# bridge.net
KiCad netlist of a schematic drawn in Altium Designer
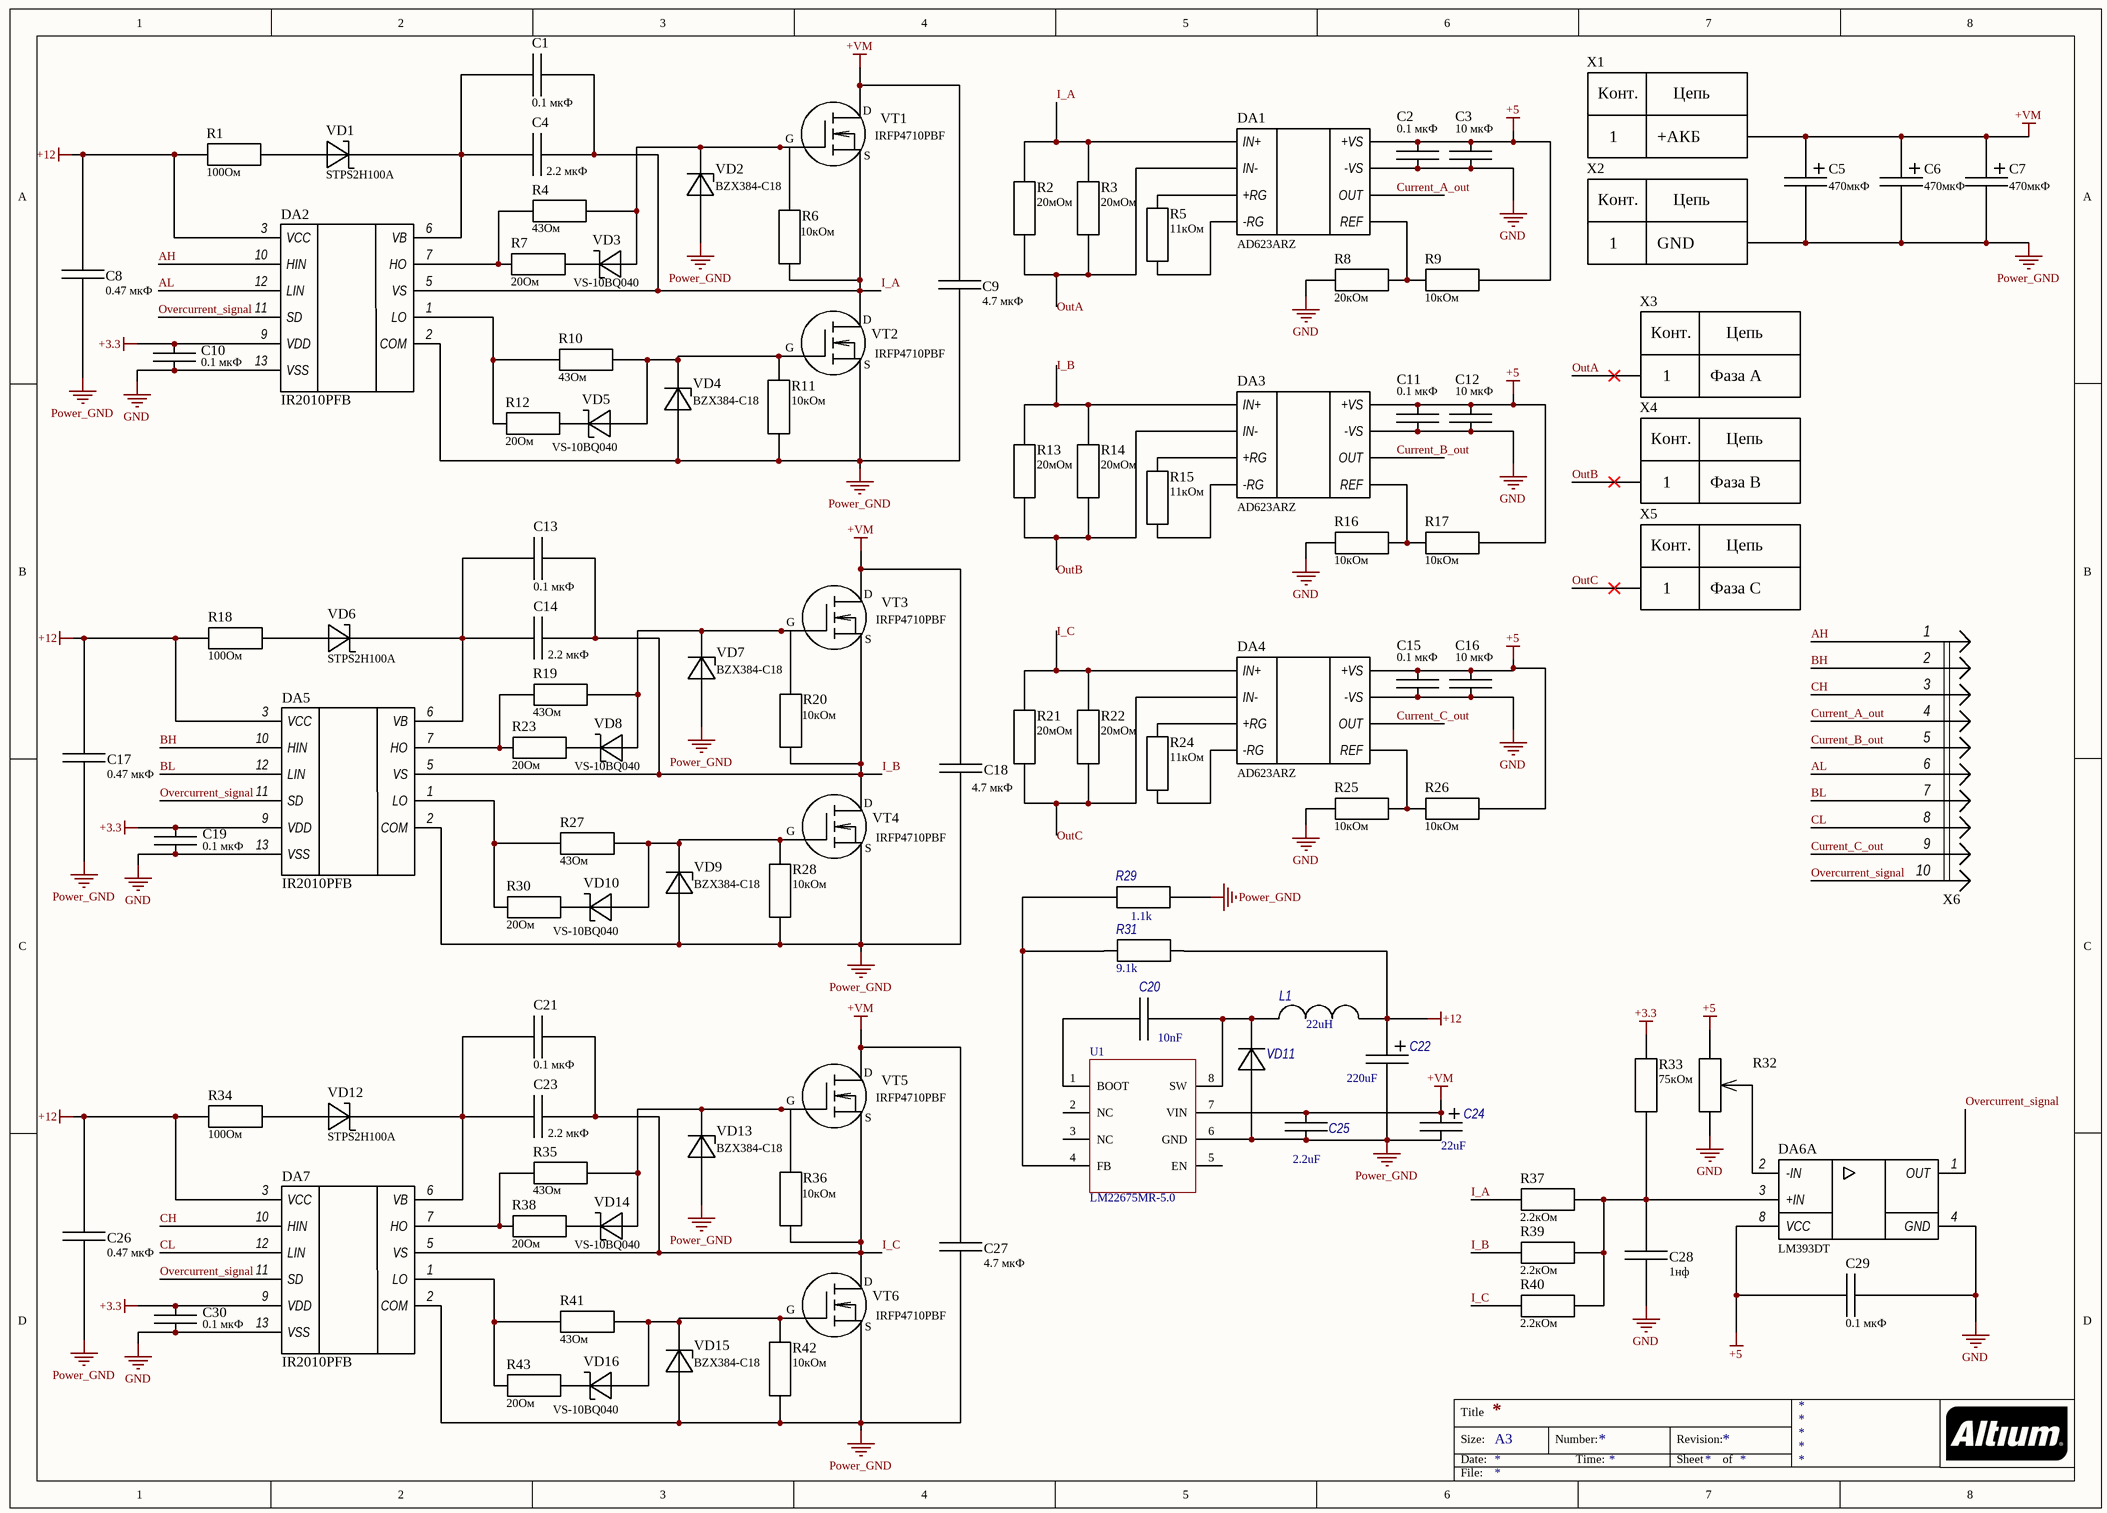
[diagram p0: bridge.SchDoc]

(export (version "E")
  (design (tool "Eeschema 10.0.6"))
  (components
    (comp (ref "C1")
      (value "0.1 мкФ")
      (footprint "0805")
      (fields (field (name "Comment") "Capacitor"))
      (libsource (lib "InvertorSchLib") (part "Capacitor"))
    )
    (comp (ref "C2")
      (value "0.1 мкФ")
      (footprint "C0603C")
      (fields (field (name "Comment") "Capacitor"))
      (libsource (lib "InvertorSchLib") (part "Capacitor"))
    )
    (comp (ref "C3")
      (value "10 мкФ")
      (footprint "0805")
      (fields (field (name "Comment") "Capacitor"))
      (libsource (lib "InvertorSchLib") (part "Capacitor"))
    )
    (comp (ref "C4")
      (value "2.2 мкФ")
      (footprint "1812С")
      (fields (field (name "Comment") "Capacitor"))
      (libsource (lib "InvertorSchLib") (part "Capacitor"))
    )
    (comp (ref "C5")
      (value "470мкФ")
      (footprint "CAP-10")
      (fields (field (name "Comment") "Сapacitor pol"))
      (libsource (lib "InvertorSchLib") (part "Сapacitor pol"))
    )
    (comp (ref "C6")
      (value "470мкФ")
      (footprint "CAP-10")
      (fields (field (name "Comment") "Сapacitor pol"))
      (libsource (lib "InvertorSchLib") (part "Сapacitor pol"))
    )
    (comp (ref "C7")
      (value "470мкФ")
      (footprint "CAP-10")
      (fields (field (name "Comment") "Сapacitor pol"))
      (libsource (lib "InvertorSchLib") (part "Сapacitor pol"))
    )
    (comp (ref "C8")
      (value "0.47 мкФ")
      (footprint "0805")
      (fields (field (name "Comment") "Capacitor"))
      (libsource (lib "InvertorSchLib") (part "Capacitor"))
    )
    (comp (ref "C9")
      (value "4.7 мкФ")
      (footprint "2220С")
      (fields (field (name "Comment") "Capacitor"))
      (libsource (lib "InvertorSchLib") (part "Capacitor"))
    )
    (comp (ref "C10")
      (value "0.1 мкФ")
      (footprint "C0603C")
      (fields (field (name "Comment") "Capacitor"))
      (libsource (lib "InvertorSchLib") (part "Capacitor"))
    )
    (comp (ref "C11")
      (value "0.1 мкФ")
      (footprint "C0603C")
      (fields (field (name "Comment") "Capacitor"))
      (libsource (lib "InvertorSchLib") (part "Capacitor"))
    )
    (comp (ref "C12")
      (value "10 мкФ")
      (footprint "0805")
      (fields (field (name "Comment") "Capacitor"))
      (libsource (lib "InvertorSchLib") (part "Capacitor"))
    )
    (comp (ref "C13")
      (value "0.1 мкФ")
      (footprint "0805")
      (fields (field (name "Comment") "Capacitor"))
      (libsource (lib "InvertorSchLib") (part "Capacitor"))
    )
    (comp (ref "C14")
      (value "2.2 мкФ")
      (footprint "1812С")
      (fields (field (name "Comment") "Capacitor"))
      (libsource (lib "InvertorSchLib") (part "Capacitor"))
    )
    (comp (ref "C15")
      (value "0.1 мкФ")
      (footprint "C0603C")
      (fields (field (name "Comment") "Capacitor"))
      (libsource (lib "InvertorSchLib") (part "Capacitor"))
    )
    (comp (ref "C16")
      (value "10 мкФ")
      (footprint "0805")
      (fields (field (name "Comment") "Capacitor"))
      (libsource (lib "InvertorSchLib") (part "Capacitor"))
    )
    (comp (ref "C17")
      (value "0.47 мкФ")
      (footprint "0805")
      (fields (field (name "Comment") "Capacitor"))
      (libsource (lib "InvertorSchLib") (part "Capacitor"))
    )
    (comp (ref "C18")
      (value "4.7 мкФ")
      (footprint "2220С")
      (fields (field (name "Comment") "Capacitor"))
      (libsource (lib "InvertorSchLib") (part "Capacitor"))
    )
    (comp (ref "C19")
      (value "0.1 мкФ")
      (footprint "C0603C")
      (fields (field (name "Comment") "Capacitor"))
      (libsource (lib "InvertorSchLib") (part "Capacitor"))
    )
    (comp (ref "C20") (value "10nF") (footprint "C0805C") (libsource (lib "Schlib1") (part "Cap")))
    (comp (ref "C21")
      (value "0.1 мкФ")
      (footprint "0805")
      (fields (field (name "Comment") "Capacitor"))
      (libsource (lib "InvertorSchLib") (part "Capacitor"))
    )
    (comp (ref "C22") (value "220uF") (footprint "CAP-8x12") (libsource (lib "Schlib1") (part "CapPol")))
    (comp (ref "C23")
      (value "2.2 мкФ")
      (footprint "1812С")
      (fields (field (name "Comment") "Capacitor"))
      (libsource (lib "InvertorSchLib") (part "Capacitor"))
    )
    (comp (ref "C24") (value "22uF") (footprint "CAP-К50-35") (libsource (lib "Schlib1") (part "CapPol")))
    (comp (ref "C25") (value "2.2uF") (footprint "C1812C") (libsource (lib "Schlib1") (part "Cap")))
    (comp (ref "C26")
      (value "0.47 мкФ")
      (footprint "0805")
      (fields (field (name "Comment") "Capacitor"))
      (libsource (lib "InvertorSchLib") (part "Capacitor"))
    )
    (comp (ref "C27")
      (value "4.7 мкФ")
      (footprint "2220С")
      (fields (field (name "Comment") "Capacitor"))
      (libsource (lib "InvertorSchLib") (part "Capacitor"))
    )
    (comp (ref "C28")
      (value "1нф")
      (footprint "C1206C")
      (fields (field (name "Comment") "Capacitor"))
      (libsource (lib "InvertorSchLib") (part "Capacitor"))
    )
    (comp (ref "C29")
      (value "0.1 мкФ")
      (footprint "C0603C")
      (fields (field (name "Comment") "Capacitor"))
      (libsource (lib "InvertorSchLib") (part "Capacitor"))
    )
    (comp (ref "C30")
      (value "0.1 мкФ")
      (footprint "C0603C")
      (fields (field (name "Comment") "Capacitor"))
      (libsource (lib "InvertorSchLib") (part "Capacitor"))
    )
    (comp (ref "DA1")
      (value "AD623ARZ")
      (footprint "SO8")
      (libsource (lib "InvertorSchLib") (part "AD623ARZ-R7"))
    )
    (comp (ref "DA2")
      (value "IR2010PFB")
      (footprint "DIP14")
      (libsource (lib "InvertorSchLib") (part "IR2010SPFB"))
    )
    (comp (ref "DA3")
      (value "AD623ARZ")
      (footprint "SO8")
      (libsource (lib "InvertorSchLib") (part "AD623ARZ-R7"))
    )
    (comp (ref "DA4")
      (value "AD623ARZ")
      (footprint "SO8")
      (libsource (lib "InvertorSchLib") (part "AD623ARZ-R7"))
    )
    (comp (ref "DA5")
      (value "IR2010PFB")
      (footprint "DIP14")
      (libsource (lib "InvertorSchLib") (part "IR2010SPFB"))
    )
    (comp (ref "DA6")
      (value "LM393DT")
      (footprint "SO8")
      (libsource (lib "InvertorSchLib") (part "Comparator"))
    )
    (comp (ref "DA7")
      (value "IR2010PFB")
      (footprint "DIP14")
      (libsource (lib "InvertorSchLib") (part "IR2010SPFB"))
    )
    (comp (ref "L1") (value "22uH") (footprint "IND0488-G-E") (libsource (lib "Schlib1") (part "Inductor")))
    (comp (ref "R1")
      (value "100Ом")
      (footprint "2512R")
      (fields (field (name "POWER") "1Вт") (field (name "Comment") "Resistor"))
      (libsource (lib "InvertorSchLib") (part "Resistor"))
    )
    (comp (ref "R2")
      (value "20мОм")
      (footprint "2816R")
      (fields (field (name "POWER") "2В") (field (name "Comment") "Resistor"))
      (libsource (lib "InvertorSchLib") (part "Resistor"))
    )
    (comp (ref "R3")
      (value "20мОм")
      (footprint "2816R")
      (fields (field (name "POWER") "2В") (field (name "Comment") "Resistor"))
      (libsource (lib "InvertorSchLib") (part "Resistor"))
    )
    (comp (ref "R4")
      (value "43Ом")
      (footprint "2512R")
      (fields (field (name "POWER") "1Вт") (field (name "Comment") "Resistor"))
      (libsource (lib "InvertorSchLib") (part "Resistor"))
    )
    (comp (ref "R5")
      (value "11кОм")
      (footprint "0402R")
      (fields (field (name "Comment") "Resistor"))
      (libsource (lib "InvertorSchLib") (part "Resistor"))
    )
    (comp (ref "R6")
      (value "10кОм")
      (footprint "0402R")
      (fields (field (name "POWER") "0.062") (field (name "Comment") "Resistor"))
      (libsource (lib "InvertorSchLib") (part "Resistor"))
    )
    (comp (ref "R7")
      (value "20Ом")
      (footprint "2512R")
      (fields (field (name "POWER") "1Вт") (field (name "Comment") "Resistor"))
      (libsource (lib "InvertorSchLib") (part "Resistor"))
    )
    (comp (ref "R8")
      (value "20кОм")
      (footprint "0402R")
      (fields (field (name "POWER") "0.062") (field (name "Comment") "Resistor"))
      (libsource (lib "InvertorSchLib") (part "Resistor"))
    )
    (comp (ref "R9")
      (value "10кОм")
      (footprint "0402R")
      (fields (field (name "POWER") "0.062") (field (name "Comment") "Resistor"))
      (libsource (lib "InvertorSchLib") (part "Resistor"))
    )
    (comp (ref "R10")
      (value "43Ом")
      (footprint "2512R")
      (fields (field (name "POWER") "1Вт") (field (name "Comment") "Resistor"))
      (libsource (lib "InvertorSchLib") (part "Resistor"))
    )
    (comp (ref "R11")
      (value "10кОм")
      (footprint "0402R")
      (fields (field (name "POWER") "0.062") (field (name "Comment") "Resistor"))
      (libsource (lib "InvertorSchLib") (part "Resistor"))
    )
    (comp (ref "R12")
      (value "20Ом")
      (footprint "2512R")
      (fields (field (name "POWER") "1Вт") (field (name "Comment") "Resistor"))
      (libsource (lib "InvertorSchLib") (part "Resistor"))
    )
    (comp (ref "R13")
      (value "20мОм")
      (footprint "2816R")
      (fields (field (name "POWER") "2В") (field (name "Comment") "Resistor"))
      (libsource (lib "InvertorSchLib") (part "Resistor"))
    )
    (comp (ref "R14")
      (value "20мОм")
      (footprint "2816R")
      (fields (field (name "POWER") "2В") (field (name "Comment") "Resistor"))
      (libsource (lib "InvertorSchLib") (part "Resistor"))
    )
    (comp (ref "R15")
      (value "11кОм")
      (footprint "0402R")
      (fields (field (name "Comment") "Resistor"))
      (libsource (lib "InvertorSchLib") (part "Resistor"))
    )
    (comp (ref "R16")
      (value "10кОм")
      (footprint "0402R")
      (fields (field (name "POWER") "0.062") (field (name "Comment") "Resistor"))
      (libsource (lib "InvertorSchLib") (part "Resistor"))
    )
    (comp (ref "R17")
      (value "10кОм")
      (footprint "0402R")
      (fields (field (name "POWER") "0.062") (field (name "Comment") "Resistor"))
      (libsource (lib "InvertorSchLib") (part "Resistor"))
    )
    (comp (ref "R18")
      (value "100Ом")
      (footprint "2512R")
      (fields (field (name "POWER") "1Вт") (field (name "Comment") "Resistor"))
      (libsource (lib "InvertorSchLib") (part "Resistor"))
    )
    (comp (ref "R19")
      (value "43Ом")
      (footprint "2512R")
      (fields (field (name "POWER") "1Вт") (field (name "Comment") "Resistor"))
      (libsource (lib "InvertorSchLib") (part "Resistor"))
    )
    (comp (ref "R20")
      (value "10кОм")
      (footprint "0402R")
      (fields (field (name "POWER") "0.062") (field (name "Comment") "Resistor"))
      (libsource (lib "InvertorSchLib") (part "Resistor"))
    )
    (comp (ref "R21")
      (value "20мОм")
      (footprint "2816R")
      (fields (field (name "POWER") "2В") (field (name "Comment") "Resistor"))
      (libsource (lib "InvertorSchLib") (part "Resistor"))
    )
    (comp (ref "R22")
      (value "20мОм")
      (footprint "2816R")
      (fields (field (name "POWER") "2В") (field (name "Comment") "Resistor"))
      (libsource (lib "InvertorSchLib") (part "Resistor"))
    )
    (comp (ref "R23")
      (value "20Ом")
      (footprint "2512R")
      (fields (field (name "POWER") "1Вт") (field (name "Comment") "Resistor"))
      (libsource (lib "InvertorSchLib") (part "Resistor"))
    )
    (comp (ref "R24")
      (value "11кОм")
      (footprint "0402R")
      (fields (field (name "Comment") "Resistor"))
      (libsource (lib "InvertorSchLib") (part "Resistor"))
    )
    (comp (ref "R25")
      (value "10кОм")
      (footprint "0402R")
      (fields (field (name "POWER") "0.062") (field (name "Comment") "Resistor"))
      (libsource (lib "InvertorSchLib") (part "Resistor"))
    )
    (comp (ref "R26")
      (value "10кОм")
      (footprint "0402R")
      (fields (field (name "POWER") "0.062") (field (name "Comment") "Resistor"))
      (libsource (lib "InvertorSchLib") (part "Resistor"))
    )
    (comp (ref "R27")
      (value "43Ом")
      (footprint "2512R")
      (fields (field (name "POWER") "1Вт") (field (name "Comment") "Resistor"))
      (libsource (lib "InvertorSchLib") (part "Resistor"))
    )
    (comp (ref "R28")
      (value "10кОм")
      (footprint "0402R")
      (fields (field (name "POWER") "0.062") (field (name "Comment") "Resistor"))
      (libsource (lib "InvertorSchLib") (part "Resistor"))
    )
    (comp (ref "R29") (value "1.1k") (footprint "C0805R") (libsource (lib "Schlib1") (part "res")))
    (comp (ref "R30")
      (value "20Ом")
      (footprint "2512R")
      (fields (field (name "POWER") "1Вт") (field (name "Comment") "Resistor"))
      (libsource (lib "InvertorSchLib") (part "Resistor"))
    )
    (comp (ref "R31") (value "9.1k") (footprint "C0805R") (libsource (lib "Schlib1") (part "res")))
    (comp (ref "R32") (value "pot") (footprint "3296W") (libsource (lib "InvertorSchLib") (part "pot")))
    (comp (ref "R33")
      (value "75кОм")
      (footprint "0402R")
      (fields (field (name "POWER") "0.062") (field (name "Comment") "Resistor"))
      (libsource (lib "InvertorSchLib") (part "Resistor"))
    )
    (comp (ref "R34")
      (value "100Ом")
      (footprint "2512R")
      (fields (field (name "POWER") "1Вт") (field (name "Comment") "Resistor"))
      (libsource (lib "InvertorSchLib") (part "Resistor"))
    )
    (comp (ref "R35")
      (value "43Ом")
      (footprint "2512R")
      (fields (field (name "POWER") "1Вт") (field (name "Comment") "Resistor"))
      (libsource (lib "InvertorSchLib") (part "Resistor"))
    )
    (comp (ref "R36")
      (value "10кОм")
      (footprint "0402R")
      (fields (field (name "POWER") "0.062") (field (name "Comment") "Resistor"))
      (libsource (lib "InvertorSchLib") (part "Resistor"))
    )
    (comp (ref "R37")
      (value "2.2кОм")
      (footprint "0402R")
      (fields (field (name "POWER") "0.062") (field (name "Comment") "Resistor"))
      (libsource (lib "InvertorSchLib") (part "Resistor"))
    )
    (comp (ref "R38")
      (value "20Ом")
      (footprint "2512R")
      (fields (field (name "POWER") "1Вт") (field (name "Comment") "Resistor"))
      (libsource (lib "InvertorSchLib") (part "Resistor"))
    )
    (comp (ref "R39")
      (value "2.2кОм")
      (footprint "0402R")
      (fields (field (name "POWER") "0.062") (field (name "Comment") "Resistor"))
      (libsource (lib "InvertorSchLib") (part "Resistor"))
    )
    (comp (ref "R40")
      (value "2.2кОм")
      (footprint "0402R")
      (fields (field (name "POWER") "0.062") (field (name "Comment") "Resistor"))
      (libsource (lib "InvertorSchLib") (part "Resistor"))
    )
    (comp (ref "R41")
      (value "43Ом")
      (footprint "2512R")
      (fields (field (name "POWER") "1Вт") (field (name "Comment") "Resistor"))
      (libsource (lib "InvertorSchLib") (part "Resistor"))
    )
    (comp (ref "R42")
      (value "10кОм")
      (footprint "0402R")
      (fields (field (name "POWER") "0.062") (field (name "Comment") "Resistor"))
      (libsource (lib "InvertorSchLib") (part "Resistor"))
    )
    (comp (ref "R43")
      (value "20Ом")
      (footprint "2512R")
      (fields (field (name "POWER") "1Вт") (field (name "Comment") "Resistor"))
      (libsource (lib "InvertorSchLib") (part "Resistor"))
    )
    (comp (ref "U1")
      (value "LM22675MR-5.0")
      (footprint "LM22675MR-5.0/NOPB")
      (libsource (lib "Schlib1") (part "LM22675MR-5.0/NOPB"))
    )
    (comp (ref "VD1")
      (value "STPS2H100A")
      (footprint "D0-124AC")
      (libsource (lib "InvertorSchLib") (part "Bootstrap diode"))
    )
    (comp (ref "VD2")
      (value "BZX384-C18")
      (footprint "SOD323")
      (libsource (lib "InvertorSchLib") (part "Zener diode"))
    )
    (comp (ref "VD3")
      (value "VS-10BQ040")
      (footprint "D0-124AC")
      (libsource (lib "InvertorSchLib") (part "Shotki"))
    )
    (comp (ref "VD4")
      (value "BZX384-C18")
      (footprint "SOD323")
      (libsource (lib "InvertorSchLib") (part "Zener diode"))
    )
    (comp (ref "VD5")
      (value "VS-10BQ040")
      (footprint "D0-124AC")
      (libsource (lib "InvertorSchLib") (part "Shotki"))
    )
    (comp (ref "VD6")
      (value "STPS2H100A")
      (footprint "D0-124AC")
      (libsource (lib "InvertorSchLib") (part "Bootstrap diode"))
    )
    (comp (ref "VD7")
      (value "BZX384-C18")
      (footprint "SOD323")
      (libsource (lib "InvertorSchLib") (part "Zener diode"))
    )
    (comp (ref "VD8")
      (value "VS-10BQ040")
      (footprint "D0-124AC")
      (libsource (lib "InvertorSchLib") (part "Shotki"))
    )
    (comp (ref "VD9")
      (value "BZX384-C18")
      (footprint "SOD323")
      (libsource (lib "InvertorSchLib") (part "Zener diode"))
    )
    (comp (ref "VD10")
      (value "VS-10BQ040")
      (footprint "D0-124AC")
      (libsource (lib "InvertorSchLib") (part "Shotki"))
    )
    (comp (ref "VD11") (value "~") (footprint "DO-214AA") (libsource (lib "Schlib1") (part "DIODE")))
    (comp (ref "VD12")
      (value "STPS2H100A")
      (footprint "D0-124AC")
      (libsource (lib "InvertorSchLib") (part "Bootstrap diode"))
    )
    (comp (ref "VD13")
      (value "BZX384-C18")
      (footprint "SOD323")
      (libsource (lib "InvertorSchLib") (part "Zener diode"))
    )
    (comp (ref "VD14")
      (value "VS-10BQ040")
      (footprint "D0-124AC")
      (libsource (lib "InvertorSchLib") (part "Shotki"))
    )
    (comp (ref "VD15")
      (value "BZX384-C18")
      (footprint "SOD323")
      (libsource (lib "InvertorSchLib") (part "Zener diode"))
    )
    (comp (ref "VD16")
      (value "VS-10BQ040")
      (footprint "D0-124AC")
      (libsource (lib "InvertorSchLib") (part "Shotki"))
    )
    (comp (ref "VT1")
      (value "IRFP4710PBF")
      (footprint "TO247-2")
      (libsource (lib "InvertorSchLib") (part "N-MOSFET"))
    )
    (comp (ref "VT2")
      (value "IRFP4710PBF")
      (footprint "TO247-1")
      (libsource (lib "InvertorSchLib") (part "N-MOSFET"))
    )
    (comp (ref "VT3")
      (value "IRFP4710PBF")
      (footprint "TO247-2")
      (libsource (lib "InvertorSchLib") (part "N-MOSFET"))
    )
    (comp (ref "VT4")
      (value "IRFP4710PBF")
      (footprint "TO247-1")
      (libsource (lib "InvertorSchLib") (part "N-MOSFET"))
    )
    (comp (ref "VT5")
      (value "IRFP4710PBF")
      (footprint "TO247-2")
      (libsource (lib "InvertorSchLib") (part "N-MOSFET"))
    )
    (comp (ref "VT6")
      (value "IRFP4710PBF")
      (footprint "TO247-1")
      (libsource (lib "InvertorSchLib") (part "N-MOSFET"))
    )
    (comp (ref "X1")
      (value "Connector-1")
      (footprint "PCBM4")
      (fields (field (name "NAME") "+АКБ"))
      (libsource (lib "InvertorSchLib") (part "Connector-1"))
    )
    (comp (ref "X2")
      (value "Connector-1")
      (footprint "PCBM4")
      (fields (field (name "NAME") "GND"))
      (libsource (lib "InvertorSchLib") (part "Connector-1"))
    )
    (comp (ref "X3")
      (value "Connector-1_1")
      (footprint "PCBM4")
      (fields (field (name "NAME") "Фаза А"))
      (libsource (lib "InvertorSchLib") (part "Connector-1_1"))
    )
    (comp (ref "X4")
      (value "Connector-1_1")
      (footprint "PCBM4")
      (fields (field (name "NAME") "Фаза B"))
      (libsource (lib "InvertorSchLib") (part "Connector-1_1"))
    )
    (comp (ref "X5")
      (value "Connector-1_1")
      (footprint "PCBM4")
      (fields (field (name "NAME") "Фаза C"))
      (libsource (lib "InvertorSchLib") (part "Connector-1_1"))
    )
    (comp (ref "X6")
      (value "PLS-2x5")
      (footprint "PLS-2x5")
      (libsource (lib "InvertorSchLib") (part "PLS-2x5"))
    )
  )
  (nets
    (net (code "1") (name "+3.3") (class "Default")
      (node (ref "C10") (pin "2") (pinfunction "2_2") (pintype "passive"))
      (node (ref "C19") (pin "2") (pinfunction "2_2") (pintype "passive"))
      (node (ref "C30") (pin "2") (pinfunction "2_2") (pintype "passive"))
      (node (ref "DA2") (pin "9") (pinfunction "VDD_9") (pintype "passive"))
      (node (ref "DA5") (pin "9") (pinfunction "VDD_9") (pintype "passive"))
      (node (ref "DA7") (pin "9") (pinfunction "VDD_9") (pintype "passive"))
      (node (ref "R33") (pin "2") (pinfunction "2_2") (pintype "passive"))
    )
    (net (code "2") (name "+5") (class "Default")
      (node (ref "C11") (pin "2") (pinfunction "2_2") (pintype "passive"))
      (node (ref "C12") (pin "2") (pinfunction "2_2") (pintype "passive"))
      (node (ref "C15") (pin "2") (pinfunction "2_2") (pintype "passive"))
      (node (ref "C16") (pin "2") (pinfunction "2_2") (pintype "passive"))
      (node (ref "C2") (pin "2") (pinfunction "2_2") (pintype "passive"))
      (node (ref "C29") (pin "1") (pinfunction "1_1") (pintype "passive"))
      (node (ref "C3") (pin "2") (pinfunction "2_2") (pintype "passive"))
      (node (ref "DA1") (pin "7") (pinfunction "+VS_7") (pintype "passive"))
      (node (ref "DA3") (pin "7") (pinfunction "+VS_7") (pintype "passive"))
      (node (ref "DA4") (pin "7") (pinfunction "+VS_7") (pintype "passive"))
      (node (ref "DA6") (pin "8") (pinfunction "VCC_8") (pintype "passive"))
      (node (ref "R17") (pin "2") (pinfunction "2_2") (pintype "passive"))
      (node (ref "R26") (pin "2") (pinfunction "2_2") (pintype "passive"))
      (node (ref "R32") (pin "1") (pinfunction "1_1") (pintype "passive"))
      (node (ref "R9") (pin "2") (pinfunction "2_2") (pintype "passive"))
    )
    (net (code "3") (name "+12") (class "Default")
      (node (ref "C17") (pin "2") (pinfunction "2_2") (pintype "passive"))
      (node (ref "C22") (pin "1") (pinfunction "1_1") (pintype "passive"))
      (node (ref "C26") (pin "2") (pinfunction "2_2") (pintype "passive"))
      (node (ref "C8") (pin "2") (pinfunction "2_2") (pintype "passive"))
      (node (ref "DA2") (pin "3") (pinfunction "VCC_3") (pintype "passive"))
      (node (ref "DA5") (pin "3") (pinfunction "VCC_3") (pintype "passive"))
      (node (ref "DA7") (pin "3") (pinfunction "VCC_3") (pintype "passive"))
      (node (ref "L1") (pin "2") (pinfunction "2_2") (pintype "passive"))
      (node (ref "R1") (pin "2") (pinfunction "2_2") (pintype "passive"))
      (node (ref "R18") (pin "2") (pinfunction "2_2") (pintype "passive"))
      (node (ref "R31") (pin "2") (pinfunction "2_2") (pintype "passive"))
      (node (ref "R34") (pin "2") (pinfunction "2_2") (pintype "passive"))
    )
    (net (code "4") (name "+VM") (class "Default")
      (node (ref "C18") (pin "2") (pinfunction "2_2") (pintype "passive"))
      (node (ref "C24") (pin "1") (pinfunction "1_1") (pintype "passive"))
      (node (ref "C25") (pin "1") (pinfunction "1_1") (pintype "passive"))
      (node (ref "C27") (pin "2") (pinfunction "2_2") (pintype "passive"))
      (node (ref "C5") (pin "1") (pinfunction "1_1") (pintype "passive"))
      (node (ref "C6") (pin "1") (pinfunction "1_1") (pintype "passive"))
      (node (ref "C7") (pin "1") (pinfunction "1_1") (pintype "passive"))
      (node (ref "C9") (pin "2") (pinfunction "2_2") (pintype "passive"))
      (node (ref "U1") (pin "7") (pinfunction "VIN_7") (pintype "passive"))
      (node (ref "VT1") (pin "D") (pinfunction "D_D") (pintype "passive"))
      (node (ref "VT3") (pin "D") (pinfunction "D_D") (pintype "passive"))
      (node (ref "VT5") (pin "D") (pinfunction "D_D") (pintype "passive"))
      (node (ref "X1") (pin "1") (pinfunction "1_1") (pintype "passive"))
    )
    (net (code "5") (name "/AH") (class "Default")
      (node (ref "DA2") (pin "10") (pinfunction "HIN_10") (pintype "passive"))
      (node (ref "X6") (pin "1") (pinfunction "1_1") (pintype "passive"))
    )
    (net (code "6") (name "/AL") (class "Default")
      (node (ref "DA2") (pin "12") (pinfunction "LIN_12") (pintype "passive"))
      (node (ref "X6") (pin "6") (pinfunction "6_6") (pintype "passive"))
    )
    (net (code "7") (name "/BH") (class "Default")
      (node (ref "DA5") (pin "10") (pinfunction "HIN_10") (pintype "passive"))
      (node (ref "X6") (pin "2") (pinfunction "2_2") (pintype "passive"))
    )
    (net (code "8") (name "/BL") (class "Default")
      (node (ref "DA5") (pin "12") (pinfunction "LIN_12") (pintype "passive"))
      (node (ref "X6") (pin "7") (pinfunction "7_7") (pintype "passive"))
    )
    (net (code "9") (name "/CH") (class "Default")
      (node (ref "DA7") (pin "10") (pinfunction "HIN_10") (pintype "passive"))
      (node (ref "X6") (pin "3") (pinfunction "3_3") (pintype "passive"))
    )
    (net (code "10") (name "/CL") (class "Default")
      (node (ref "DA7") (pin "12") (pinfunction "LIN_12") (pintype "passive"))
      (node (ref "X6") (pin "8") (pinfunction "8_8") (pintype "passive"))
    )
    (net (code "11") (name "/Current_A_out") (class "Default")
      (node (ref "DA1") (pin "6") (pinfunction "OUT_6") (pintype "passive"))
      (node (ref "X6") (pin "4") (pinfunction "4_4") (pintype "passive"))
    )
    (net (code "12") (name "/Current_B_out") (class "Default")
      (node (ref "DA3") (pin "6") (pinfunction "OUT_6") (pintype "passive"))
      (node (ref "X6") (pin "5") (pinfunction "5_5") (pintype "passive"))
    )
    (net (code "13") (name "/Current_C_out") (class "Default")
      (node (ref "DA4") (pin "6") (pinfunction "OUT_6") (pintype "passive"))
      (node (ref "X6") (pin "9") (pinfunction "9_9") (pintype "passive"))
    )
    (net (code "14") (name "/I_A") (class "Default")
      (node (ref "C1") (pin "1") (pinfunction "1_1") (pintype "passive"))
      (node (ref "C4") (pin "2") (pinfunction "2_2") (pintype "passive"))
      (node (ref "DA1") (pin "3") (pinfunction "IN+_3") (pintype "passive"))
      (node (ref "DA2") (pin "5") (pinfunction "VS_5") (pintype "passive"))
      (node (ref "R2") (pin "1") (pinfunction "1_1") (pintype "passive"))
      (node (ref "R3") (pin "1") (pinfunction "1_1") (pintype "passive"))
      (node (ref "R37") (pin "1") (pinfunction "1_1") (pintype "passive"))
      (node (ref "R6") (pin "2") (pinfunction "2_2") (pintype "passive"))
      (node (ref "VT1") (pin "S") (pinfunction "S_S") (pintype "passive"))
      (node (ref "VT2") (pin "D") (pinfunction "D_D") (pintype "passive"))
    )
    (net (code "15") (name "/I_B") (class "Default")
      (node (ref "C13") (pin "1") (pinfunction "1_1") (pintype "passive"))
      (node (ref "C14") (pin "2") (pinfunction "2_2") (pintype "passive"))
      (node (ref "DA3") (pin "3") (pinfunction "IN+_3") (pintype "passive"))
      (node (ref "DA5") (pin "5") (pinfunction "VS_5") (pintype "passive"))
      (node (ref "R13") (pin "1") (pinfunction "1_1") (pintype "passive"))
      (node (ref "R14") (pin "1") (pinfunction "1_1") (pintype "passive"))
      (node (ref "R20") (pin "2") (pinfunction "2_2") (pintype "passive"))
      (node (ref "R39") (pin "1") (pinfunction "1_1") (pintype "passive"))
      (node (ref "VT3") (pin "S") (pinfunction "S_S") (pintype "passive"))
      (node (ref "VT4") (pin "D") (pinfunction "D_D") (pintype "passive"))
    )
    (net (code "16") (name "/I_C") (class "Default")
      (node (ref "C21") (pin "1") (pinfunction "1_1") (pintype "passive"))
      (node (ref "C23") (pin "2") (pinfunction "2_2") (pintype "passive"))
      (node (ref "DA4") (pin "3") (pinfunction "IN+_3") (pintype "passive"))
      (node (ref "DA7") (pin "5") (pinfunction "VS_5") (pintype "passive"))
      (node (ref "R21") (pin "1") (pinfunction "1_1") (pintype "passive"))
      (node (ref "R22") (pin "1") (pinfunction "1_1") (pintype "passive"))
      (node (ref "R36") (pin "2") (pinfunction "2_2") (pintype "passive"))
      (node (ref "R40") (pin "1") (pinfunction "1_1") (pintype "passive"))
      (node (ref "VT5") (pin "S") (pinfunction "S_S") (pintype "passive"))
      (node (ref "VT6") (pin "D") (pinfunction "D_D") (pintype "passive"))
    )
    (net (code "17") (name "/OutA") (class "Default")
      (node (ref "DA1") (pin "2") (pinfunction "IN-_2") (pintype "passive"))
      (node (ref "R2") (pin "2") (pinfunction "2_2") (pintype "passive"))
      (node (ref "R3") (pin "2") (pinfunction "2_2") (pintype "passive"))
      (node (ref "X3") (pin "1") (pinfunction "1_1") (pintype "passive"))
    )
    (net (code "18") (name "/OutB") (class "Default")
      (node (ref "DA3") (pin "2") (pinfunction "IN-_2") (pintype "passive"))
      (node (ref "R13") (pin "2") (pinfunction "2_2") (pintype "passive"))
      (node (ref "R14") (pin "2") (pinfunction "2_2") (pintype "passive"))
      (node (ref "X4") (pin "1") (pinfunction "1_1") (pintype "passive"))
    )
    (net (code "19") (name "/OutC") (class "Default")
      (node (ref "DA4") (pin "2") (pinfunction "IN-_2") (pintype "passive"))
      (node (ref "R21") (pin "2") (pinfunction "2_2") (pintype "passive"))
      (node (ref "R22") (pin "2") (pinfunction "2_2") (pintype "passive"))
      (node (ref "X5") (pin "1") (pinfunction "1_1") (pintype "passive"))
    )
    (net (code "20") (name "/Overcurrent_signal") (class "Default")
      (node (ref "DA2") (pin "11") (pinfunction "SD_11") (pintype "passive"))
      (node (ref "DA5") (pin "11") (pinfunction "SD_11") (pintype "passive"))
      (node (ref "DA6") (pin "1") (pinfunction "OUT_1") (pintype "passive"))
      (node (ref "DA7") (pin "11") (pinfunction "SD_11") (pintype "passive"))
      (node (ref "X6") (pin "10") (pinfunction "10_10") (pintype "passive"))
    )
    (net (code "21") (name "GND") (class "Default")
      (node (ref "C10") (pin "1") (pinfunction "1_1") (pintype "passive"))
      (node (ref "C11") (pin "1") (pinfunction "1_1") (pintype "passive"))
      (node (ref "C12") (pin "1") (pinfunction "1_1") (pintype "passive"))
      (node (ref "C15") (pin "1") (pinfunction "1_1") (pintype "passive"))
      (node (ref "C16") (pin "1") (pinfunction "1_1") (pintype "passive"))
      (node (ref "C19") (pin "1") (pinfunction "1_1") (pintype "passive"))
      (node (ref "C2") (pin "1") (pinfunction "1_1") (pintype "passive"))
      (node (ref "C28") (pin "1") (pinfunction "1_1") (pintype "passive"))
      (node (ref "C29") (pin "2") (pinfunction "2_2") (pintype "passive"))
      (node (ref "C3") (pin "1") (pinfunction "1_1") (pintype "passive"))
      (node (ref "C30") (pin "1") (pinfunction "1_1") (pintype "passive"))
      (node (ref "DA1") (pin "4") (pinfunction "-VS_4") (pintype "passive"))
      (node (ref "DA2") (pin "13") (pinfunction "VSS_13") (pintype "passive"))
      (node (ref "DA3") (pin "4") (pinfunction "-VS_4") (pintype "passive"))
      (node (ref "DA4") (pin "4") (pinfunction "-VS_4") (pintype "passive"))
      (node (ref "DA5") (pin "13") (pinfunction "VSS_13") (pintype "passive"))
      (node (ref "DA6") (pin "4") (pinfunction "GND_4") (pintype "passive"))
      (node (ref "DA7") (pin "13") (pinfunction "VSS_13") (pintype "passive"))
      (node (ref "R16") (pin "1") (pinfunction "1_1") (pintype "passive"))
      (node (ref "R25") (pin "1") (pinfunction "1_1") (pintype "passive"))
      (node (ref "R32") (pin "3") (pinfunction "3_3") (pintype "passive"))
      (node (ref "R8") (pin "1") (pinfunction "1_1") (pintype "passive"))
    )
    (net (code "22") (name "Net-(DA1-+RG)") (class "Default")
      (node (ref "DA1") (pin "8") (pinfunction "+RG_8") (pintype "passive"))
      (node (ref "R5") (pin "1") (pinfunction "1_1") (pintype "passive"))
    )
    (net (code "23") (name "Net-(DA1--RG)") (class "Default")
      (node (ref "DA1") (pin "1") (pinfunction "-RG_1") (pintype "passive"))
      (node (ref "R5") (pin "2") (pinfunction "2_2") (pintype "passive"))
    )
    (net (code "24") (name "Net-(DA1-REF)") (class "Default")
      (node (ref "DA1") (pin "5") (pinfunction "REF_5") (pintype "passive"))
      (node (ref "R8") (pin "2") (pinfunction "2_2") (pintype "passive"))
      (node (ref "R9") (pin "1") (pinfunction "1_1") (pintype "passive"))
    )
    (net (code "25") (name "Net-(DA2-HO)") (class "Default")
      (node (ref "DA2") (pin "7") (pinfunction "HO_7") (pintype "passive"))
      (node (ref "R4") (pin "2") (pinfunction "2_2") (pintype "passive"))
      (node (ref "R7") (pin "2") (pinfunction "2_2") (pintype "passive"))
    )
    (net (code "26") (name "Net-(DA2-LO)") (class "Default")
      (node (ref "DA2") (pin "1") (pinfunction "LO_1") (pintype "passive"))
      (node (ref "R10") (pin "2") (pinfunction "2_2") (pintype "passive"))
      (node (ref "R12") (pin "2") (pinfunction "2_2") (pintype "passive"))
    )
    (net (code "27") (name "Net-(DA2-VB)") (class "Default")
      (node (ref "C1") (pin "2") (pinfunction "2_2") (pintype "passive"))
      (node (ref "C4") (pin "1") (pinfunction "1_1") (pintype "passive"))
      (node (ref "DA2") (pin "6") (pinfunction "VB_6") (pintype "passive"))
      (node (ref "VD1") (pin "C") (pinfunction "C_C") (pintype "passive"))
    )
    (net (code "28") (name "Net-(DA3-+RG)") (class "Default")
      (node (ref "DA3") (pin "8") (pinfunction "+RG_8") (pintype "passive"))
      (node (ref "R15") (pin "1") (pinfunction "1_1") (pintype "passive"))
    )
    (net (code "29") (name "Net-(DA3--RG)") (class "Default")
      (node (ref "DA3") (pin "1") (pinfunction "-RG_1") (pintype "passive"))
      (node (ref "R15") (pin "2") (pinfunction "2_2") (pintype "passive"))
    )
    (net (code "30") (name "Net-(DA3-REF)") (class "Default")
      (node (ref "DA3") (pin "5") (pinfunction "REF_5") (pintype "passive"))
      (node (ref "R16") (pin "2") (pinfunction "2_2") (pintype "passive"))
      (node (ref "R17") (pin "1") (pinfunction "1_1") (pintype "passive"))
    )
    (net (code "31") (name "Net-(DA4-+RG)") (class "Default")
      (node (ref "DA4") (pin "8") (pinfunction "+RG_8") (pintype "passive"))
      (node (ref "R24") (pin "1") (pinfunction "1_1") (pintype "passive"))
    )
    (net (code "32") (name "Net-(DA4--RG)") (class "Default")
      (node (ref "DA4") (pin "1") (pinfunction "-RG_1") (pintype "passive"))
      (node (ref "R24") (pin "2") (pinfunction "2_2") (pintype "passive"))
    )
    (net (code "33") (name "Net-(DA4-REF)") (class "Default")
      (node (ref "DA4") (pin "5") (pinfunction "REF_5") (pintype "passive"))
      (node (ref "R25") (pin "2") (pinfunction "2_2") (pintype "passive"))
      (node (ref "R26") (pin "1") (pinfunction "1_1") (pintype "passive"))
    )
    (net (code "34") (name "Net-(DA5-HO)") (class "Default")
      (node (ref "DA5") (pin "7") (pinfunction "HO_7") (pintype "passive"))
      (node (ref "R19") (pin "2") (pinfunction "2_2") (pintype "passive"))
      (node (ref "R23") (pin "2") (pinfunction "2_2") (pintype "passive"))
    )
    (net (code "35") (name "Net-(DA5-LO)") (class "Default")
      (node (ref "DA5") (pin "1") (pinfunction "LO_1") (pintype "passive"))
      (node (ref "R27") (pin "2") (pinfunction "2_2") (pintype "passive"))
      (node (ref "R30") (pin "2") (pinfunction "2_2") (pintype "passive"))
    )
    (net (code "36") (name "Net-(DA5-VB)") (class "Default")
      (node (ref "C13") (pin "2") (pinfunction "2_2") (pintype "passive"))
      (node (ref "C14") (pin "1") (pinfunction "1_1") (pintype "passive"))
      (node (ref "DA5") (pin "6") (pinfunction "VB_6") (pintype "passive"))
      (node (ref "VD6") (pin "C") (pinfunction "C_C") (pintype "passive"))
    )
    (net (code "37") (name "Net-(DA6A-+IN)") (class "Default")
      (node (ref "C28") (pin "2") (pinfunction "2_2") (pintype "passive"))
      (node (ref "DA6") (pin "3") (pinfunction "+IN_3") (pintype "passive"))
      (node (ref "R33") (pin "1") (pinfunction "1_1") (pintype "passive"))
      (node (ref "R37") (pin "2") (pinfunction "2_2") (pintype "passive"))
      (node (ref "R39") (pin "2") (pinfunction "2_2") (pintype "passive"))
      (node (ref "R40") (pin "2") (pinfunction "2_2") (pintype "passive"))
    )
    (net (code "38") (name "Net-(DA6A--IN)") (class "Default")
      (node (ref "DA6") (pin "2") (pinfunction "-IN_2") (pintype "passive"))
      (node (ref "R32") (pin "2") (pinfunction "2_2") (pintype "passive"))
    )
    (net (code "39") (name "Net-(DA7-HO)") (class "Default")
      (node (ref "DA7") (pin "7") (pinfunction "HO_7") (pintype "passive"))
      (node (ref "R35") (pin "2") (pinfunction "2_2") (pintype "passive"))
      (node (ref "R38") (pin "2") (pinfunction "2_2") (pintype "passive"))
    )
    (net (code "40") (name "Net-(DA7-LO)") (class "Default")
      (node (ref "DA7") (pin "1") (pinfunction "LO_1") (pintype "passive"))
      (node (ref "R41") (pin "2") (pinfunction "2_2") (pintype "passive"))
      (node (ref "R43") (pin "2") (pinfunction "2_2") (pintype "passive"))
    )
    (net (code "41") (name "Net-(DA7-VB)") (class "Default")
      (node (ref "C21") (pin "2") (pinfunction "2_2") (pintype "passive"))
      (node (ref "C23") (pin "1") (pinfunction "1_1") (pintype "passive"))
      (node (ref "DA7") (pin "6") (pinfunction "VB_6") (pintype "passive"))
      (node (ref "VD12") (pin "C") (pinfunction "C_C") (pintype "passive"))
    )
    (net (code "42") (name "Net-(R1-Pad1)") (class "Default")
      (node (ref "R1") (pin "1") (pinfunction "1_1") (pintype "passive"))
      (node (ref "VD1") (pin "A") (pinfunction "A_A") (pintype "passive"))
    )
    (net (code "43") (name "Net-(R4-Pad1)") (class "Default")
      (node (ref "R4") (pin "1") (pinfunction "1_1") (pintype "passive"))
      (node (ref "R6") (pin "1") (pinfunction "1_1") (pintype "passive"))
      (node (ref "VD2") (pin "C") (pinfunction "C_C") (pintype "passive"))
      (node (ref "VD3") (pin "A") (pinfunction "A_A") (pintype "passive"))
      (node (ref "VT1") (pin "G") (pinfunction "G_G") (pintype "passive"))
    )
    (net (code "44") (name "Net-(R7-Pad1)") (class "Default")
      (node (ref "R7") (pin "1") (pinfunction "1_1") (pintype "passive"))
      (node (ref "VD3") (pin "C") (pinfunction "C_C") (pintype "passive"))
    )
    (net (code "45") (name "Net-(R10-Pad1)") (class "Default")
      (node (ref "R10") (pin "1") (pinfunction "1_1") (pintype "passive"))
      (node (ref "R11") (pin "1") (pinfunction "1_1") (pintype "passive"))
      (node (ref "VD4") (pin "C") (pinfunction "C_C") (pintype "passive"))
      (node (ref "VD5") (pin "A") (pinfunction "A_A") (pintype "passive"))
      (node (ref "VT2") (pin "G") (pinfunction "G_G") (pintype "passive"))
    )
    (net (code "46") (name "Net-(R12-Pad1)") (class "Default")
      (node (ref "R12") (pin "1") (pinfunction "1_1") (pintype "passive"))
      (node (ref "VD5") (pin "C") (pinfunction "C_C") (pintype "passive"))
    )
    (net (code "47") (name "Net-(R18-Pad1)") (class "Default")
      (node (ref "R18") (pin "1") (pinfunction "1_1") (pintype "passive"))
      (node (ref "VD6") (pin "A") (pinfunction "A_A") (pintype "passive"))
    )
    (net (code "48") (name "Net-(R19-Pad1)") (class "Default")
      (node (ref "R19") (pin "1") (pinfunction "1_1") (pintype "passive"))
      (node (ref "R20") (pin "1") (pinfunction "1_1") (pintype "passive"))
      (node (ref "VD7") (pin "C") (pinfunction "C_C") (pintype "passive"))
      (node (ref "VD8") (pin "A") (pinfunction "A_A") (pintype "passive"))
      (node (ref "VT3") (pin "G") (pinfunction "G_G") (pintype "passive"))
    )
    (net (code "49") (name "Net-(R23-Pad1)") (class "Default")
      (node (ref "R23") (pin "1") (pinfunction "1_1") (pintype "passive"))
      (node (ref "VD8") (pin "C") (pinfunction "C_C") (pintype "passive"))
    )
    (net (code "50") (name "Net-(R27-Pad1)") (class "Default")
      (node (ref "R27") (pin "1") (pinfunction "1_1") (pintype "passive"))
      (node (ref "R28") (pin "1") (pinfunction "1_1") (pintype "passive"))
      (node (ref "VD10") (pin "A") (pinfunction "A_A") (pintype "passive"))
      (node (ref "VD9") (pin "C") (pinfunction "C_C") (pintype "passive"))
      (node (ref "VT4") (pin "G") (pinfunction "G_G") (pintype "passive"))
    )
    (net (code "51") (name "Net-(R30-Pad1)") (class "Default")
      (node (ref "R30") (pin "1") (pinfunction "1_1") (pintype "passive"))
      (node (ref "VD10") (pin "C") (pinfunction "C_C") (pintype "passive"))
    )
    (net (code "52") (name "Net-(R34-Pad1)") (class "Default")
      (node (ref "R34") (pin "1") (pinfunction "1_1") (pintype "passive"))
      (node (ref "VD12") (pin "A") (pinfunction "A_A") (pintype "passive"))
    )
    (net (code "53") (name "Net-(R35-Pad1)") (class "Default")
      (node (ref "R35") (pin "1") (pinfunction "1_1") (pintype "passive"))
      (node (ref "R36") (pin "1") (pinfunction "1_1") (pintype "passive"))
      (node (ref "VD13") (pin "C") (pinfunction "C_C") (pintype "passive"))
      (node (ref "VD14") (pin "A") (pinfunction "A_A") (pintype "passive"))
      (node (ref "VT5") (pin "G") (pinfunction "G_G") (pintype "passive"))
    )
    (net (code "54") (name "Net-(R38-Pad1)") (class "Default")
      (node (ref "R38") (pin "1") (pinfunction "1_1") (pintype "passive"))
      (node (ref "VD14") (pin "C") (pinfunction "C_C") (pintype "passive"))
    )
    (net (code "55") (name "Net-(R41-Pad1)") (class "Default")
      (node (ref "R41") (pin "1") (pinfunction "1_1") (pintype "passive"))
      (node (ref "R42") (pin "1") (pinfunction "1_1") (pintype "passive"))
      (node (ref "VD15") (pin "C") (pinfunction "C_C") (pintype "passive"))
      (node (ref "VD16") (pin "A") (pinfunction "A_A") (pintype "passive"))
      (node (ref "VT6") (pin "G") (pinfunction "G_G") (pintype "passive"))
    )
    (net (code "56") (name "Net-(R43-Pad1)") (class "Default")
      (node (ref "R43") (pin "1") (pinfunction "1_1") (pintype "passive"))
      (node (ref "VD16") (pin "C") (pinfunction "C_C") (pintype "passive"))
    )
    (net (code "57") (name "Net-(U1-BOOT)") (class "Default")
      (node (ref "C20") (pin "1") (pinfunction "1_1") (pintype "passive"))
      (node (ref "U1") (pin "1") (pinfunction "BOOT_1") (pintype "passive"))
    )
    (net (code "58") (name "Net-(U1-FB)") (class "Default")
      (node (ref "R29") (pin "2") (pinfunction "2_2") (pintype "passive"))
      (node (ref "R31") (pin "1") (pinfunction "1_1") (pintype "passive"))
      (node (ref "U1") (pin "4") (pinfunction "FB_4") (pintype "passive"))
    )
    (net (code "59") (name "Net-(U1-SW)") (class "Default")
      (node (ref "C20") (pin "2") (pinfunction "2_2") (pintype "passive"))
      (node (ref "L1") (pin "1") (pinfunction "1_1") (pintype "passive"))
      (node (ref "U1") (pin "8") (pinfunction "SW_8") (pintype "passive"))
      (node (ref "VD11") (pin "C") (pinfunction "C_C") (pintype "passive"))
    )
    (net (code "60") (name "Power_GND") (class "Default")
      (node (ref "C17") (pin "1") (pinfunction "1_1") (pintype "passive"))
      (node (ref "C18") (pin "1") (pinfunction "1_1") (pintype "passive"))
      (node (ref "C22") (pin "2") (pinfunction "2_2") (pintype "passive"))
      (node (ref "C24") (pin "2") (pinfunction "2_2") (pintype "passive"))
      (node (ref "C25") (pin "2") (pinfunction "2_2") (pintype "passive"))
      (node (ref "C26") (pin "1") (pinfunction "1_1") (pintype "passive"))
      (node (ref "C27") (pin "1") (pinfunction "1_1") (pintype "passive"))
      (node (ref "C5") (pin "2") (pinfunction "2_2") (pintype "passive"))
      (node (ref "C6") (pin "2") (pinfunction "2_2") (pintype "passive"))
      (node (ref "C7") (pin "2") (pinfunction "2_2") (pintype "passive"))
      (node (ref "C8") (pin "1") (pinfunction "1_1") (pintype "passive"))
      (node (ref "C9") (pin "1") (pinfunction "1_1") (pintype "passive"))
      (node (ref "DA2") (pin "2") (pinfunction "COM_2") (pintype "passive"))
      (node (ref "DA5") (pin "2") (pinfunction "COM_2") (pintype "passive"))
      (node (ref "DA7") (pin "2") (pinfunction "COM_2") (pintype "passive"))
      (node (ref "R11") (pin "2") (pinfunction "2_2") (pintype "passive"))
      (node (ref "R28") (pin "2") (pinfunction "2_2") (pintype "passive"))
      (node (ref "R29") (pin "1") (pinfunction "1_1") (pintype "passive"))
      (node (ref "R42") (pin "2") (pinfunction "2_2") (pintype "passive"))
      (node (ref "U1") (pin "6") (pinfunction "GND_6") (pintype "passive"))
      (node (ref "VD11") (pin "A") (pinfunction "A_A") (pintype "passive"))
      (node (ref "VD13") (pin "A") (pinfunction "A_A") (pintype "passive"))
      (node (ref "VD15") (pin "A") (pinfunction "A_A") (pintype "passive"))
      (node (ref "VD2") (pin "A") (pinfunction "A_A") (pintype "passive"))
      (node (ref "VD4") (pin "A") (pinfunction "A_A") (pintype "passive"))
      (node (ref "VD7") (pin "A") (pinfunction "A_A") (pintype "passive"))
      (node (ref "VD9") (pin "A") (pinfunction "A_A") (pintype "passive"))
      (node (ref "VT2") (pin "S") (pinfunction "S_S") (pintype "passive"))
      (node (ref "VT4") (pin "S") (pinfunction "S_S") (pintype "passive"))
      (node (ref "VT6") (pin "S") (pinfunction "S_S") (pintype "passive"))
      (node (ref "X2") (pin "1") (pinfunction "1_1") (pintype "passive"))
    )
    (net (code "61") (name "unconnected-(U1-EN-Pad5)") (class "Default")
      (node (ref "U1") (pin "5") (pinfunction "EN_5") (pintype "passive"))
    )
    (net (code "62") (name "unconnected-(U1-NC-Pad2)") (class "Default")
      (node (ref "U1") (pin "2") (pinfunction "NC_2") (pintype "passive"))
    )
    (net (code "63") (name "unconnected-(U1-NC-Pad3)") (class "Default")
      (node (ref "U1") (pin "3") (pinfunction "NC_3") (pintype "passive"))
    )
  )
)
